# Fluffy-1A.net
KiCad netlist of a schematic drawn in EAGLE
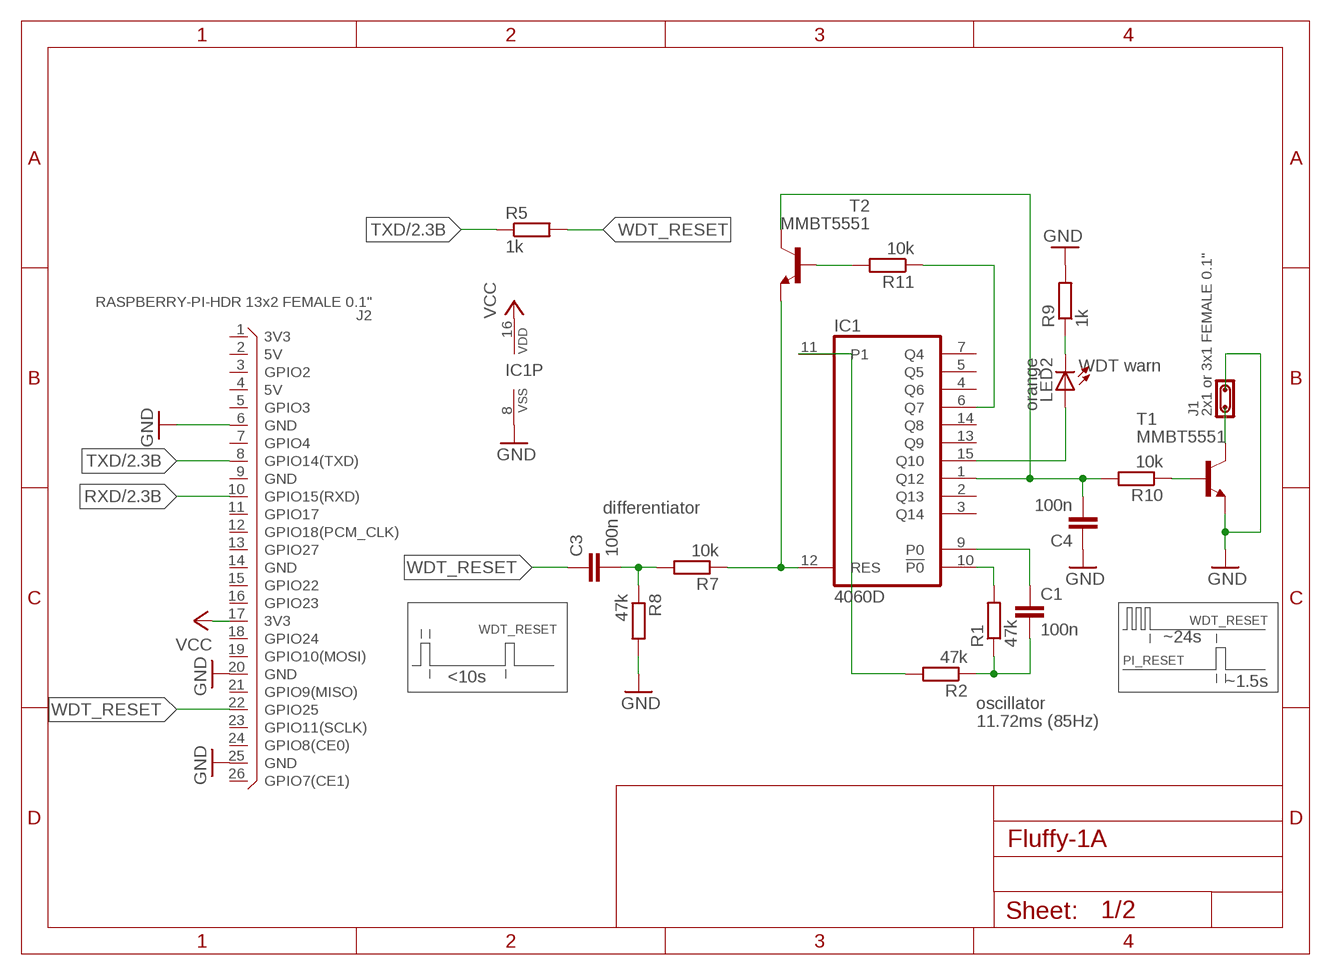
[diagram p0: schematic, sheet 1]
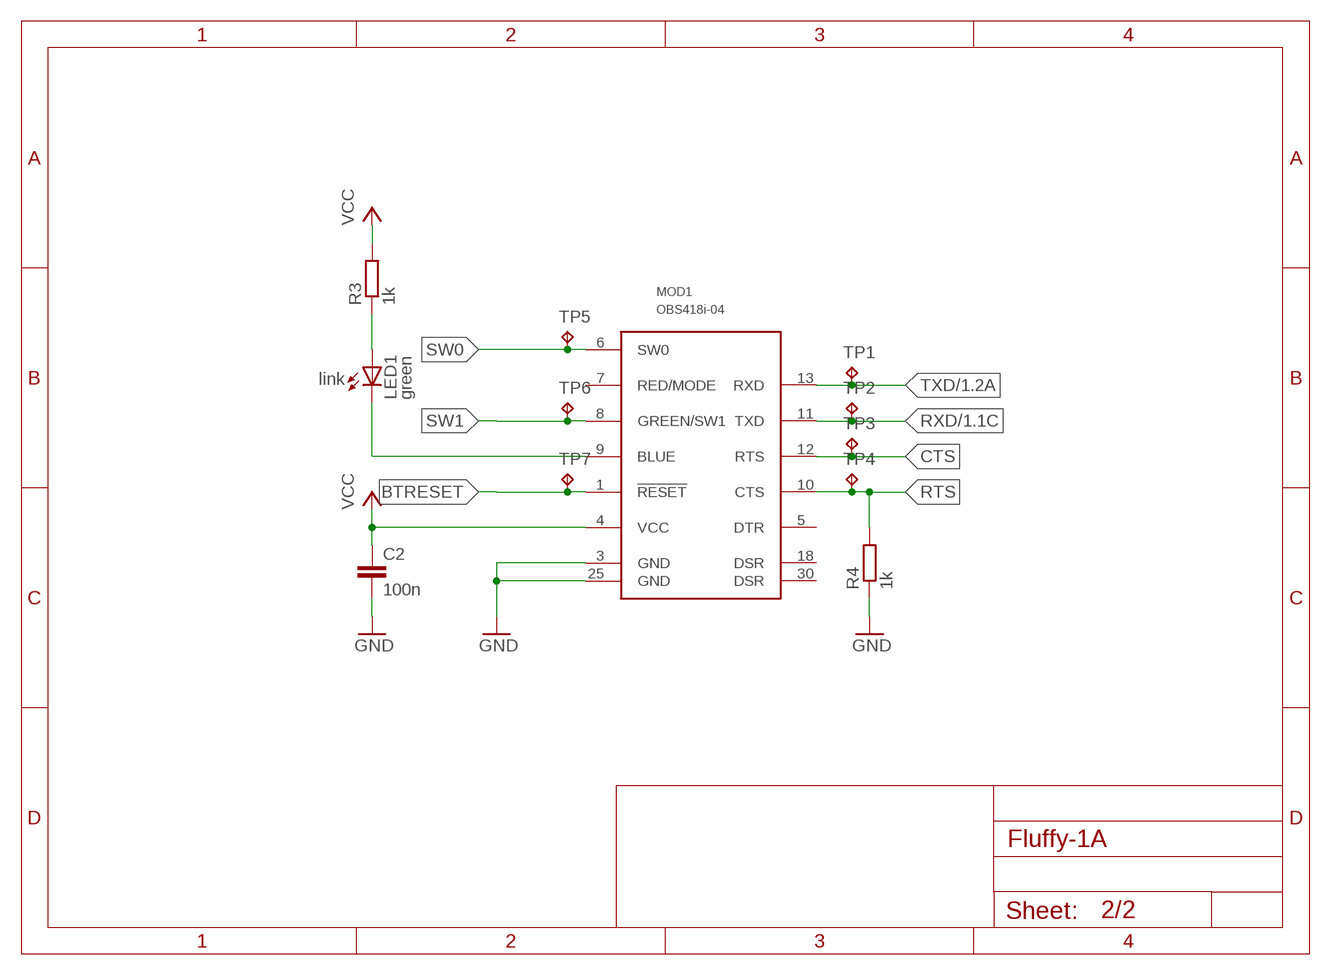
[diagram p1: schematic, sheet 2]

(export (version "E")
  (design (tool "Eeschema 10.0.6"))
  (components
    (comp (ref "C1")
      (value "100n")
      (footprint "eagle-import:C0805K")
      (libsource (lib "eagle-import") (part "C-EUC0805K"))
    )
    (comp (ref "C3")
      (value "100n")
      (footprint "eagle-import:C0805K")
      (libsource (lib "eagle-import") (part "C-EUC0805K"))
    )
    (comp (ref "C4")
      (value "100n")
      (footprint "eagle-import:C0805K")
      (libsource (lib "eagle-import") (part "C-EUC0805K"))
    )
    (comp (ref "IC1")
      (value "4060D")
      (footprint "eagle-import:SO16")
      (libsource (lib "eagle-import") (part "4060D"))
    )
    (comp (ref "J1")
      (value "2x1 or 3x1 FEMALE 0.1\"")
      (footprint "eagle-import:JP02N")
      (libsource (lib "eagle-import") (part "JP02"))
    )
    (comp (ref "J2")
      (value "RASPBERRY-PI-HDR 13x2 FEMALE 0.1\"")
      (footprint "eagle-import:X26R-DIL")
      (libsource (lib "eagle-import") (part "RASPBERRY-PI-HDR"))
    )
    (comp (ref "LED2")
      (value "orange")
      (footprint "eagle-import:CHIPLED_0805")
      (libsource (lib "eagle-import") (part "LEDCHIPLED_0805"))
    )
    (comp (ref "R1")
      (value "47k")
      (footprint "eagle-import:R0805")
      (libsource (lib "eagle-import") (part "R-EU_R0805"))
    )
    (comp (ref "R2")
      (value "47k")
      (footprint "eagle-import:R0805")
      (libsource (lib "eagle-import") (part "R-EU_R0805"))
    )
    (comp (ref "R5")
      (value "1k")
      (footprint "eagle-import:R0805")
      (libsource (lib "eagle-import") (part "R-EU_R0805"))
    )
    (comp (ref "R7")
      (value "10k")
      (footprint "eagle-import:R0805")
      (libsource (lib "eagle-import") (part "R-EU_R0805"))
    )
    (comp (ref "R8")
      (value "47k")
      (footprint "eagle-import:R0805")
      (libsource (lib "eagle-import") (part "R-EU_R0805"))
    )
    (comp (ref "R9")
      (value "1k")
      (footprint "eagle-import:R0805")
      (libsource (lib "eagle-import") (part "R-EU_R0805"))
    )
    (comp (ref "R10")
      (value "10k")
      (footprint "eagle-import:R0805")
      (libsource (lib "eagle-import") (part "R-EU_R0805"))
    )
    (comp (ref "R11")
      (value "10k")
      (footprint "eagle-import:R0805")
      (libsource (lib "eagle-import") (part "R-EU_R0805"))
    )
    (comp (ref "T1")
      (value "MMBT5551")
      (footprint "eagle-import:SOT23-BEC")
      (libsource (lib "eagle-import") (part "-NPN-SOT23-BECMMBT5551LT1"))
    )
    (comp (ref "T2")
      (value "MMBT5551")
      (footprint "eagle-import:SOT23-BEC")
      (libsource (lib "eagle-import") (part "-NPN-SOT23-BECMMBT5551LT1"))
    )
    (comp (ref "C2")
      (value "100n")
      (footprint "eagle-import:C0805K")
      (libsource (lib "eagle-import") (part "C-EUC0805K"))
    )
    (comp (ref "LED1")
      (value "green")
      (footprint "eagle-import:CHIPLED_0805")
      (libsource (lib "eagle-import") (part "LEDCHIPLED_0805"))
    )
    (comp (ref "MOD1")
      (value "OBS418i-04")
      (footprint "eagle-import:OBS4X1-NOHOLES")
      (libsource (lib "eagle-import") (part "OBS-NH421-16"))
    )
    (comp (ref "R3")
      (value "1k")
      (footprint "eagle-import:R0805")
      (libsource (lib "eagle-import") (part "R-EU_R0805"))
    )
    (comp (ref "R4")
      (value "1k")
      (footprint "eagle-import:R0805")
      (libsource (lib "eagle-import") (part "R-EU_R0805"))
    )
    (comp (ref "TP1")
      (value "TPTP10SQ")
      (footprint "eagle-import:TP10SQ")
      (libsource (lib "eagle-import") (part "TPTP10SQ"))
    )
    (comp (ref "TP2")
      (value "TPTP10SQ")
      (footprint "eagle-import:TP10SQ")
      (libsource (lib "eagle-import") (part "TPTP10SQ"))
    )
    (comp (ref "TP3")
      (value "TPTP10SQ")
      (footprint "eagle-import:TP10SQ")
      (libsource (lib "eagle-import") (part "TPTP10SQ"))
    )
    (comp (ref "TP4")
      (value "TPTP10SQ")
      (footprint "eagle-import:TP10SQ")
      (libsource (lib "eagle-import") (part "TPTP10SQ"))
    )
    (comp (ref "TP5")
      (value "TPTP10SQ")
      (footprint "eagle-import:TP10SQ")
      (libsource (lib "eagle-import") (part "TPTP10SQ"))
    )
    (comp (ref "TP6")
      (value "TPTP10SQ")
      (footprint "eagle-import:TP10SQ")
      (libsource (lib "eagle-import") (part "TPTP10SQ"))
    )
    (comp (ref "TP7")
      (value "TPTP10SQ")
      (footprint "eagle-import:TP10SQ")
      (libsource (lib "eagle-import") (part "TPTP10SQ"))
    )
  )
  (nets
    (net (code "1") (name "BTRESET") (class "Default")
      (node (ref "MOD1") (pin "1") (pinfunction "~{RESET}_1") (pintype "input"))
      (node (ref "TP7") (pin "TP") (pinfunction "TP_TP") (pintype "input"))
    )
    (net (code "2") (name "CTS") (class "Default")
      (node (ref "MOD1") (pin "12") (pinfunction "RTS_12") (pintype "passive"))
      (node (ref "TP3") (pin "TP") (pinfunction "TP_TP") (pintype "input"))
    )
    (net (code "3") (name "GND") (class "Default")
      (node (ref "C2") (pin "2") (pinfunction "2_2") (pintype "passive"))
      (node (ref "C4") (pin "1") (pinfunction "1_1") (pintype "passive"))
      (node (ref "IC1") (pin "8") (pinfunction "VSS_8") (pintype "power_in"))
      (node (ref "J1") (pin "2") (pinfunction "2_2") (pintype "bidirectional"))
      (node (ref "J2") (pin "20") (pinfunction "GND_20") (pintype "bidirectional"))
      (node (ref "J2") (pin "25") (pinfunction "GND_25") (pintype "bidirectional"))
      (node (ref "J2") (pin "6") (pinfunction "GND_6") (pintype "bidirectional"))
      (node (ref "MOD1") (pin "25") (pinfunction "GND_25") (pintype "power_in"))
      (node (ref "MOD1") (pin "3") (pinfunction "GND_3") (pintype "power_in"))
      (node (ref "R4") (pin "1") (pinfunction "1_1") (pintype "passive"))
      (node (ref "R8") (pin "2") (pinfunction "2_2") (pintype "passive"))
      (node (ref "R9") (pin "2") (pinfunction "2_2") (pintype "passive"))
      (node (ref "T1") (pin "E") (pinfunction "E_E") (pintype "passive"))
    )
    (net (code "4") (name "Net-(C1-Pad2)") (class "Default")
      (node (ref "C1") (pin "2") (pinfunction "2_2") (pintype "passive"))
      (node (ref "R1") (pin "1") (pinfunction "1_1") (pintype "passive"))
      (node (ref "R2") (pin "1") (pinfunction "1_1") (pintype "passive"))
    )
    (net (code "5") (name "Net-(C3-Pad2)") (class "Default")
      (node (ref "C3") (pin "2") (pinfunction "2_2") (pintype "passive"))
      (node (ref "R7") (pin "2") (pinfunction "2_2") (pintype "passive"))
      (node (ref "R8") (pin "1") (pinfunction "1_1") (pintype "passive"))
    )
    (net (code "6") (name "Net-(IC1A-P0)") (class "Default")
      (node (ref "C1") (pin "1") (pinfunction "1_1") (pintype "passive"))
      (node (ref "IC1") (pin "9") (pinfunction "P0_9") (pintype "output"))
    )
    (net (code "7") (name "Net-(IC1A-P1)") (class "Default")
      (node (ref "IC1") (pin "11") (pinfunction "P1_11") (pintype "input"))
      (node (ref "R2") (pin "2") (pinfunction "2_2") (pintype "passive"))
    )
    (net (code "8") (name "Net-(IC1A-Q7)") (class "Default")
      (node (ref "IC1") (pin "6") (pinfunction "Q7_6") (pintype "output"))
      (node (ref "R11") (pin "1") (pinfunction "1_1") (pintype "passive"))
    )
    (net (code "9") (name "Net-(IC1A-Q10)") (class "Default")
      (node (ref "IC1") (pin "15") (pinfunction "Q10_15") (pintype "output"))
      (node (ref "LED2") (pin "A") (pinfunction "A_A") (pintype "passive"))
    )
    (net (code "10") (name "Net-(IC1A-Q12)") (class "Default")
      (node (ref "C4") (pin "2") (pinfunction "2_2") (pintype "passive"))
      (node (ref "IC1") (pin "1") (pinfunction "Q12_1") (pintype "output"))
      (node (ref "R10") (pin "2") (pinfunction "2_2") (pintype "passive"))
      (node (ref "T2") (pin "C") (pinfunction "C_C") (pintype "passive"))
    )
    (net (code "11") (name "Net-(IC1A-RES)") (class "Default")
      (node (ref "IC1") (pin "12") (pinfunction "RES_12") (pintype "input"))
      (node (ref "R7") (pin "1") (pinfunction "1_1") (pintype "passive"))
      (node (ref "T2") (pin "E") (pinfunction "E_E") (pintype "passive"))
    )
    (net (code "12") (name "Net-(IC1A-~{P0})") (class "Default")
      (node (ref "IC1") (pin "10") (pinfunction "~{P0}_10") (pintype "output"))
      (node (ref "R1") (pin "2") (pinfunction "2_2") (pintype "passive"))
    )
    (net (code "13") (name "Net-(J1-Pad1)") (class "Default")
      (node (ref "J1") (pin "1") (pinfunction "1_1") (pintype "bidirectional"))
      (node (ref "T1") (pin "C") (pinfunction "C_C") (pintype "passive"))
    )
    (net (code "14") (name "Net-(LED1-PadA)") (class "Default")
      (node (ref "LED1") (pin "A") (pinfunction "A_A") (pintype "passive"))
      (node (ref "R3") (pin "1") (pinfunction "1_1") (pintype "passive"))
    )
    (net (code "15") (name "Net-(LED2-PadC)") (class "Default")
      (node (ref "LED2") (pin "C") (pinfunction "C_C") (pintype "passive"))
      (node (ref "R9") (pin "1") (pinfunction "1_1") (pintype "passive"))
    )
    (net (code "16") (name "Net-(MOD1-BLUE)") (class "Default")
      (node (ref "LED1") (pin "C") (pinfunction "C_C") (pintype "passive"))
      (node (ref "MOD1") (pin "9") (pinfunction "BLUE_9") (pintype "passive"))
    )
    (net (code "17") (name "Net-(R10-Pad1)") (class "Default")
      (node (ref "R10") (pin "1") (pinfunction "1_1") (pintype "passive"))
      (node (ref "T1") (pin "B") (pinfunction "B_B") (pintype "passive"))
    )
    (net (code "18") (name "Net-(R11-Pad2)") (class "Default")
      (node (ref "R11") (pin "2") (pinfunction "2_2") (pintype "passive"))
      (node (ref "T2") (pin "B") (pinfunction "B_B") (pintype "passive"))
    )
    (net (code "19") (name "RTS") (class "Default")
      (node (ref "MOD1") (pin "10") (pinfunction "CTS_10") (pintype "passive"))
      (node (ref "R4") (pin "2") (pinfunction "2_2") (pintype "passive"))
      (node (ref "TP4") (pin "TP") (pinfunction "TP_TP") (pintype "input"))
    )
    (net (code "20") (name "RXD") (class "Default")
      (node (ref "J2") (pin "10") (pinfunction "GPIO15(RXD)_10") (pintype "bidirectional"))
      (node (ref "MOD1") (pin "11") (pinfunction "TXD_11") (pintype "passive"))
      (node (ref "TP2") (pin "TP") (pinfunction "TP_TP") (pintype "input"))
    )
    (net (code "21") (name "SW0") (class "Default")
      (node (ref "MOD1") (pin "6") (pinfunction "SW0_6") (pintype "bidirectional"))
      (node (ref "TP5") (pin "TP") (pinfunction "TP_TP") (pintype "input"))
    )
    (net (code "22") (name "SW1") (class "Default")
      (node (ref "MOD1") (pin "8") (pinfunction "GREEN/SW1_8") (pintype "passive"))
      (node (ref "TP6") (pin "TP") (pinfunction "TP_TP") (pintype "input"))
    )
    (net (code "23") (name "TXD") (class "Default")
      (node (ref "J2") (pin "8") (pinfunction "GPIO14(TXD)_8") (pintype "bidirectional"))
      (node (ref "MOD1") (pin "13") (pinfunction "RXD_13") (pintype "passive"))
      (node (ref "R5") (pin "1") (pinfunction "1_1") (pintype "passive"))
      (node (ref "TP1") (pin "TP") (pinfunction "TP_TP") (pintype "input"))
    )
    (net (code "24") (name "VCC") (class "Default")
      (node (ref "C2") (pin "1") (pinfunction "1_1") (pintype "passive"))
      (node (ref "IC1") (pin "16") (pinfunction "VDD_16") (pintype "power_in"))
      (node (ref "J2") (pin "17") (pinfunction "3V3_17") (pintype "bidirectional"))
      (node (ref "MOD1") (pin "4") (pinfunction "VCC_4") (pintype "power_in"))
      (node (ref "R3") (pin "2") (pinfunction "2_2") (pintype "passive"))
    )
    (net (code "25") (name "WDT_RESET") (class "Default")
      (node (ref "C3") (pin "1") (pinfunction "1_1") (pintype "passive"))
      (node (ref "J2") (pin "22") (pinfunction "GPIO25_22") (pintype "bidirectional"))
      (node (ref "R5") (pin "2") (pinfunction "2_2") (pintype "passive"))
    )
    (net (code "26") (name "unconnected-(IC1A-Q4-Pad7)") (class "Default")
      (node (ref "IC1") (pin "7") (pinfunction "Q4_7") (pintype "output"))
    )
    (net (code "27") (name "unconnected-(IC1A-Q5-Pad5)") (class "Default")
      (node (ref "IC1") (pin "5") (pinfunction "Q5_5") (pintype "output"))
    )
    (net (code "28") (name "unconnected-(IC1A-Q6-Pad4)") (class "Default")
      (node (ref "IC1") (pin "4") (pinfunction "Q6_4") (pintype "output"))
    )
    (net (code "29") (name "unconnected-(IC1A-Q8-Pad14)") (class "Default")
      (node (ref "IC1") (pin "14") (pinfunction "Q8_14") (pintype "output"))
    )
    (net (code "30") (name "unconnected-(IC1A-Q9-Pad13)") (class "Default")
      (node (ref "IC1") (pin "13") (pinfunction "Q9_13") (pintype "output"))
    )
    (net (code "31") (name "unconnected-(IC1A-Q13-Pad2)") (class "Default")
      (node (ref "IC1") (pin "2") (pinfunction "Q13_2") (pintype "output"))
    )
    (net (code "32") (name "unconnected-(IC1A-Q14-Pad3)") (class "Default")
      (node (ref "IC1") (pin "3") (pinfunction "Q14_3") (pintype "output"))
    )
    (net (code "33") (name "unconnected-(J2-3V3-Pad1)") (class "Default")
      (node (ref "J2") (pin "1") (pinfunction "3V3_1") (pintype "bidirectional"))
    )
    (net (code "34") (name "unconnected-(J2-5V-Pad2)") (class "Default")
      (node (ref "J2") (pin "2") (pinfunction "5V_2") (pintype "bidirectional"))
    )
    (net (code "35") (name "unconnected-(J2-5V-Pad4)") (class "Default")
      (node (ref "J2") (pin "4") (pinfunction "5V_4") (pintype "bidirectional"))
    )
    (net (code "36") (name "unconnected-(J2-GND-Pad9)") (class "Default")
      (node (ref "J2") (pin "9") (pinfunction "GND_9") (pintype "bidirectional"))
    )
    (net (code "37") (name "unconnected-(J2-GND-Pad14)") (class "Default")
      (node (ref "J2") (pin "14") (pinfunction "GND_14") (pintype "bidirectional"))
    )
    (net (code "38") (name "unconnected-(J2-GPIO2-Pad3)") (class "Default")
      (node (ref "J2") (pin "3") (pinfunction "GPIO2_3") (pintype "bidirectional"))
    )
    (net (code "39") (name "unconnected-(J2-GPIO3-Pad5)") (class "Default")
      (node (ref "J2") (pin "5") (pinfunction "GPIO3_5") (pintype "bidirectional"))
    )
    (net (code "40") (name "unconnected-(J2-GPIO4-Pad7)") (class "Default")
      (node (ref "J2") (pin "7") (pinfunction "GPIO4_7") (pintype "bidirectional"))
    )
    (net (code "41") (name "unconnected-(J2-GPIO7(CE1)-Pad26)") (class "Default")
      (node (ref "J2") (pin "26") (pinfunction "GPIO7(CE1)_26") (pintype "bidirectional"))
    )
    (net (code "42") (name "unconnected-(J2-GPIO8(CE0)-Pad24)") (class "Default")
      (node (ref "J2") (pin "24") (pinfunction "GPIO8(CE0)_24") (pintype "bidirectional"))
    )
    (net (code "43") (name "unconnected-(J2-GPIO9(MISO)-Pad21)") (class "Default")
      (node (ref "J2") (pin "21") (pinfunction "GPIO9(MISO)_21") (pintype "bidirectional"))
    )
    (net (code "44") (name "unconnected-(J2-GPIO10(MOSI)-Pad19)") (class "Default")
      (node (ref "J2") (pin "19") (pinfunction "GPIO10(MOSI)_19") (pintype "bidirectional"))
    )
    (net (code "45") (name "unconnected-(J2-GPIO11(SCLK)-Pad23)") (class "Default")
      (node (ref "J2") (pin "23") (pinfunction "GPIO11(SCLK)_23") (pintype "bidirectional"))
    )
    (net (code "46") (name "unconnected-(J2-GPIO17-Pad11)") (class "Default")
      (node (ref "J2") (pin "11") (pinfunction "GPIO17_11") (pintype "bidirectional"))
    )
    (net (code "47") (name "unconnected-(J2-GPIO18(PCM_CLK)-Pad12)") (class "Default")
      (node (ref "J2") (pin "12") (pinfunction "GPIO18(PCM_CLK)_12") (pintype "bidirectional"))
    )
    (net (code "48") (name "unconnected-(J2-GPIO22-Pad15)") (class "Default")
      (node (ref "J2") (pin "15") (pinfunction "GPIO22_15") (pintype "bidirectional"))
    )
    (net (code "49") (name "unconnected-(J2-GPIO23-Pad16)") (class "Default")
      (node (ref "J2") (pin "16") (pinfunction "GPIO23_16") (pintype "bidirectional"))
    )
    (net (code "50") (name "unconnected-(J2-GPIO24-Pad18)") (class "Default")
      (node (ref "J2") (pin "18") (pinfunction "GPIO24_18") (pintype "bidirectional"))
    )
    (net (code "51") (name "unconnected-(J2-GPIO27-Pad13)") (class "Default")
      (node (ref "J2") (pin "13") (pinfunction "GPIO27_13") (pintype "bidirectional"))
    )
    (net (code "52") (name "unconnected-(MOD1-DSR-Pad18)") (class "Default")
      (node (ref "MOD1") (pin "18") (pinfunction "DSR_18") (pintype "passive"))
    )
    (net (code "53") (name "unconnected-(MOD1-DSR-Pad30)") (class "Default")
      (node (ref "MOD1") (pin "30") (pinfunction "DSR_30") (pintype "passive"))
    )
    (net (code "54") (name "unconnected-(MOD1-DTR-Pad5)") (class "Default")
      (node (ref "MOD1") (pin "5") (pinfunction "DTR_5") (pintype "passive"))
    )
    (net (code "55") (name "unconnected-(MOD1-RED{slash}MODE-Pad7)") (class "Default")
      (node (ref "MOD1") (pin "7") (pinfunction "RED/MODE_7") (pintype "passive"))
    )
  )
)
